# Moteino.net
KiCad netlist of a schematic drawn in EAGLE
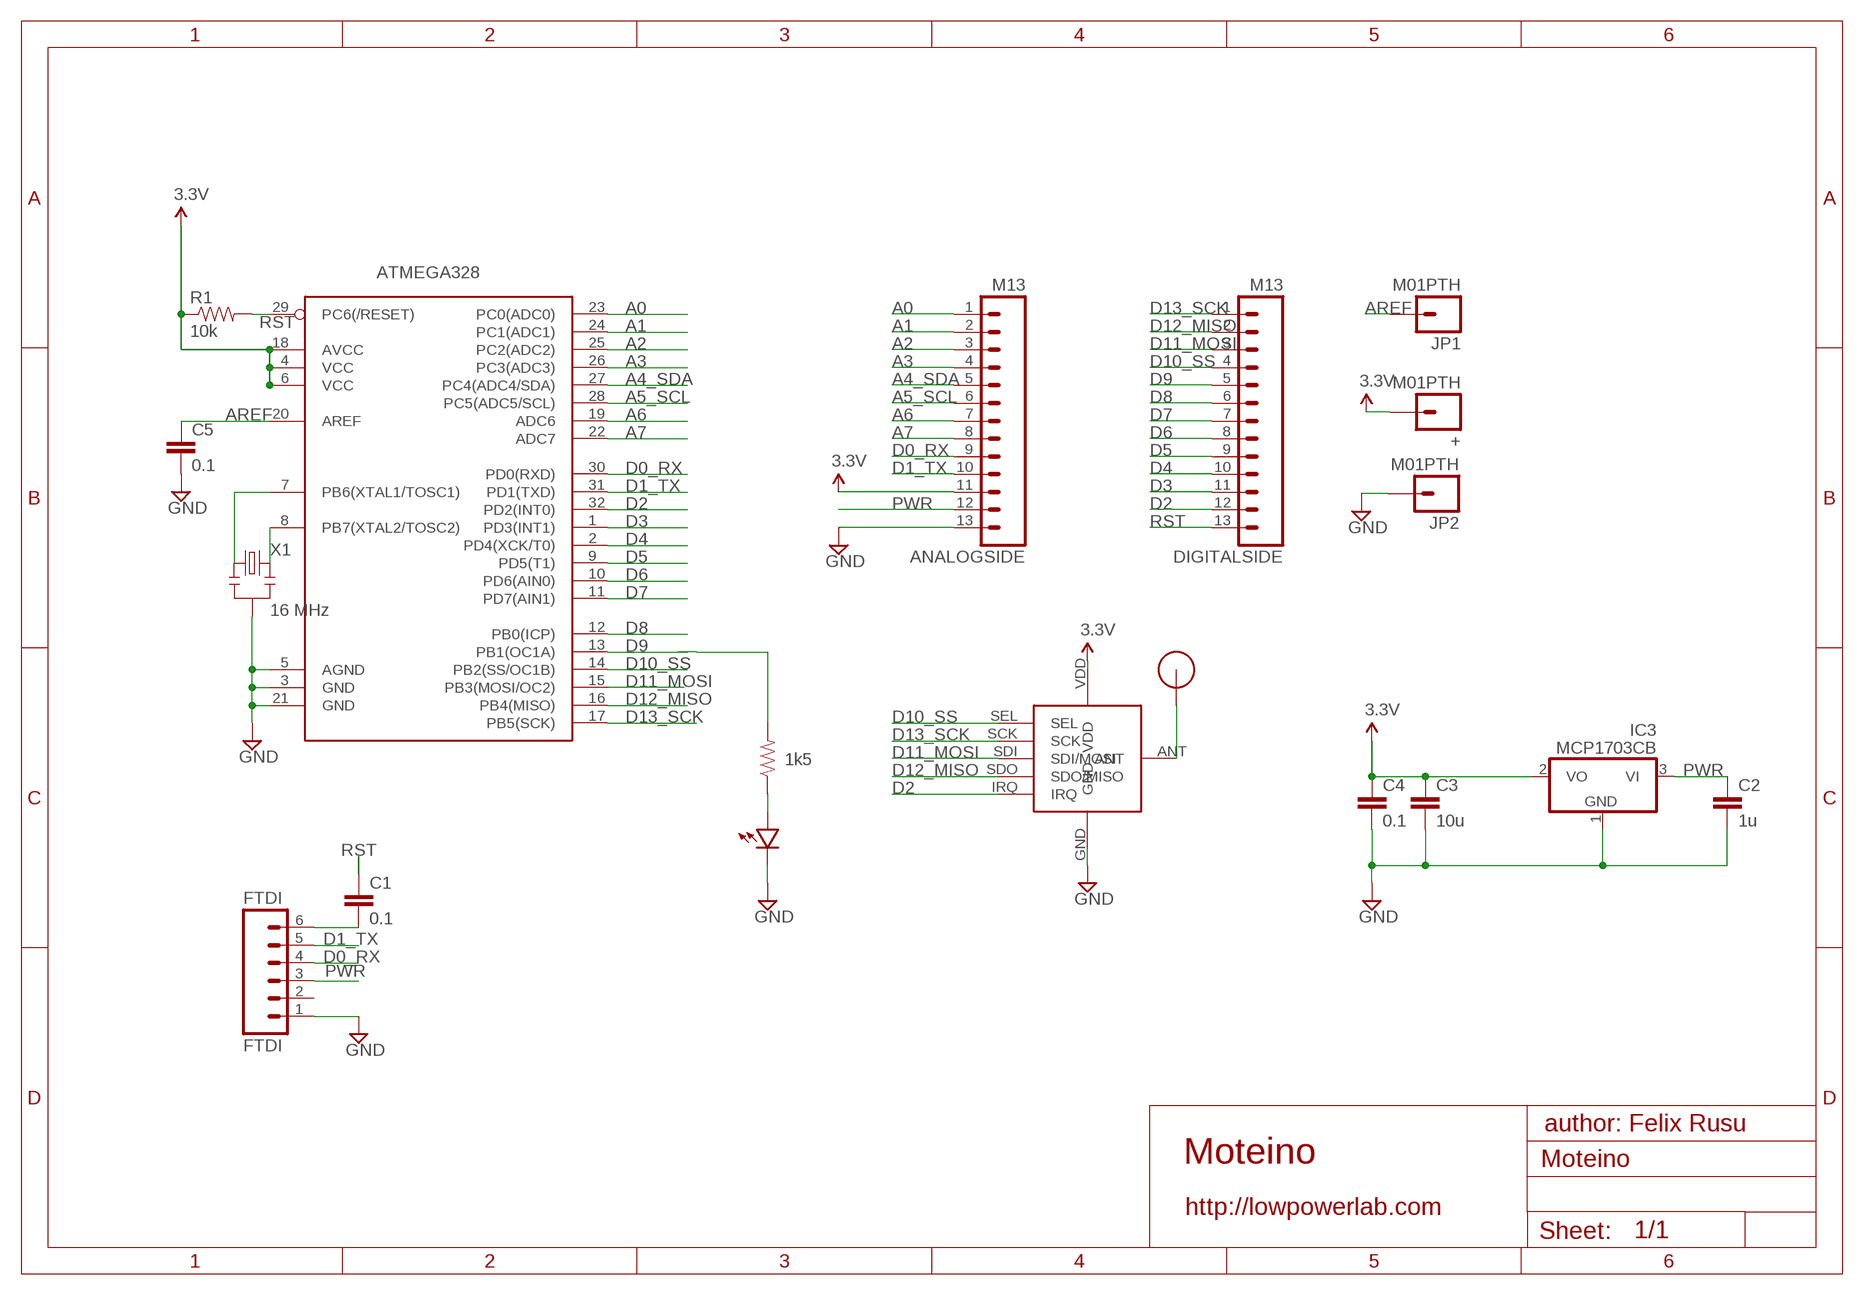
[diagram p0: schematic, sheet 1]

(export (version "E")
  (design (tool "Eeschema 10.0.6"))
  (components
    (comp (ref "+")
      (value "M01PTH")
      (footprint "eagle-import:1X01")
      (libsource (lib "eagle-import") (part "M01PTH"))
    )
    (comp (ref "ANALOGSIDE")
      (value "M13")
      (footprint "eagle-import:1X13")
      (libsource (lib "eagle-import") (part "M13"))
    )
    (comp (ref "ATMEGA328")
      (value "ATMega-328")
      (footprint "eagle-import:TQFP32-08")
      (libsource (lib "eagle-import") (part "ATMEGA168/328TQFP32"))
    )
    (comp (ref "C1")
      (value "0.1")
      (footprint "eagle-import:0603-CAP")
      (libsource (lib "eagle-import") (part "CAP0603-CAP"))
    )
    (comp (ref "C2")
      (value "1u")
      (footprint "eagle-import:0603-CAP")
      (libsource (lib "eagle-import") (part "CAP0603-CAP"))
    )
    (comp (ref "C3")
      (value "10u")
      (footprint "eagle-import:0805-CAP")
      (libsource (lib "eagle-import") (part "CAP0805-CAP"))
    )
    (comp (ref "C4")
      (value "0.1")
      (footprint "eagle-import:0603-CAP")
      (libsource (lib "eagle-import") (part "CAP0603-CAP"))
    )
    (comp (ref "C5")
      (value "0.1")
      (footprint "eagle-import:0603-CAP")
      (libsource (lib "eagle-import") (part "CAP0603-CAP"))
    )
    (comp (ref "DIGITALSIDE")
      (value "M13")
      (footprint "eagle-import:1X13")
      (libsource (lib "eagle-import") (part "M13"))
    )
    (comp (ref "FTDI")
      (value "FTDI")
      (footprint "eagle-import:1X06")
      (libsource (lib "eagle-import") (part "M06SIP"))
    )
    (comp (ref "IC3")
      (value "MCP1703CB")
      (footprint "eagle-import:SOT23")
      (libsource (lib "eagle-import") (part "MCP1703CB"))
    )
    (comp (ref "JP1")
      (value "M01PTH")
      (footprint "eagle-import:1X01")
      (libsource (lib "eagle-import") (part "M01PTH"))
    )
    (comp (ref "JP2")
      (value "M01PTH")
      (footprint "eagle-import:1X01")
      (libsource (lib "eagle-import") (part "M01PTH"))
    )
    (comp (ref "R1")
      (value "10k")
      (footprint "eagle-import:0603-RES")
      (libsource (lib "eagle-import") (part "RESISTOR0603-RES"))
    )
    (comp (ref "R2")
      (value "1k5")
      (footprint "eagle-import:0603-RES")
      (libsource (lib "eagle-import") (part "RESISTOR0603-RES"))
    )
    (comp (ref "RFM12B")
      (value "RFM12B_MINPADS")
      (footprint "eagle-import:RFM12B-MINPADS")
      (libsource (lib "eagle-import") (part "RFM12B_MINPADS"))
    )
    (comp (ref "U$1")
      (value "RFM12B_ANTENNA")
      (footprint "eagle-import:RFM12B-ANTENNA")
      (libsource (lib "eagle-import") (part "RFM12B_ANTENNA"))
    )
    (comp (ref "U$2")
      (value "LED0603")
      (footprint "eagle-import:0603-LED")
      (libsource (lib "eagle-import") (part "LED0603"))
    )
    (comp (ref "X1")
      (value "16 MHz")
      (footprint "eagle-import:RESONATOR-SMD")
      (libsource (lib "eagle-import") (part "RESONATORSMD"))
    )
  )
  (nets
    (net (code "1") (name "/A0") (class "Default")
      (node (ref "ANALOGSIDE") (pin "1") (pinfunction "1_1") (pintype "passive"))
      (node (ref "ATMEGA328") (pin "23") (pinfunction "PC0(ADC0)_23") (pintype "bidirectional"))
    )
    (net (code "2") (name "/A1") (class "Default")
      (node (ref "ANALOGSIDE") (pin "2") (pinfunction "2_2") (pintype "passive"))
      (node (ref "ATMEGA328") (pin "24") (pinfunction "PC1(ADC1)_24") (pintype "bidirectional"))
    )
    (net (code "3") (name "/A2") (class "Default")
      (node (ref "ANALOGSIDE") (pin "3") (pinfunction "3_3") (pintype "passive"))
      (node (ref "ATMEGA328") (pin "25") (pinfunction "PC2(ADC2)_25") (pintype "bidirectional"))
    )
    (net (code "4") (name "/A3") (class "Default")
      (node (ref "ANALOGSIDE") (pin "4") (pinfunction "4_4") (pintype "passive"))
      (node (ref "ATMEGA328") (pin "26") (pinfunction "PC3(ADC3)_26") (pintype "bidirectional"))
    )
    (net (code "5") (name "/A4_SDA") (class "Default")
      (node (ref "ANALOGSIDE") (pin "5") (pinfunction "5_5") (pintype "passive"))
      (node (ref "ATMEGA328") (pin "27") (pinfunction "PC4(ADC4/SDA)_27") (pintype "bidirectional"))
    )
    (net (code "6") (name "/A5_SCL") (class "Default")
      (node (ref "ANALOGSIDE") (pin "6") (pinfunction "6_6") (pintype "passive"))
      (node (ref "ATMEGA328") (pin "28") (pinfunction "PC5(ADC5/SCL)_28") (pintype "bidirectional"))
    )
    (net (code "7") (name "/A6") (class "Default")
      (node (ref "ANALOGSIDE") (pin "7") (pinfunction "7_7") (pintype "passive"))
      (node (ref "ATMEGA328") (pin "19") (pinfunction "ADC6_19") (pintype "bidirectional"))
    )
    (net (code "8") (name "/A7") (class "Default")
      (node (ref "ANALOGSIDE") (pin "8") (pinfunction "8_8") (pintype "passive"))
      (node (ref "ATMEGA328") (pin "22") (pinfunction "ADC7_22") (pintype "bidirectional"))
    )
    (net (code "9") (name "/AREF") (class "Default")
      (node (ref "ATMEGA328") (pin "20") (pinfunction "AREF_20") (pintype "bidirectional"))
      (node (ref "C5") (pin "1") (pinfunction "1_1") (pintype "passive"))
      (node (ref "JP1") (pin "1") (pinfunction "1_1") (pintype "passive"))
    )
    (net (code "10") (name "/D0_RX") (class "Default")
      (node (ref "ANALOGSIDE") (pin "9") (pinfunction "9_9") (pintype "passive"))
      (node (ref "ATMEGA328") (pin "30") (pinfunction "PD0(RXD)_30") (pintype "bidirectional"))
      (node (ref "FTDI") (pin "4") (pinfunction "4_4") (pintype "passive"))
    )
    (net (code "11") (name "/D1_TX") (class "Default")
      (node (ref "ANALOGSIDE") (pin "10") (pinfunction "10_10") (pintype "passive"))
      (node (ref "ATMEGA328") (pin "31") (pinfunction "PD1(TXD)_31") (pintype "bidirectional"))
      (node (ref "FTDI") (pin "5") (pinfunction "5_5") (pintype "passive"))
    )
    (net (code "12") (name "/D2") (class "Default")
      (node (ref "ATMEGA328") (pin "32") (pinfunction "PD2(INT0)_32") (pintype "bidirectional"))
      (node (ref "DIGITALSIDE") (pin "12") (pinfunction "12_12") (pintype "passive"))
      (node (ref "RFM12B") (pin "IRQ") (pinfunction "IRQ_IRQ") (pintype "bidirectional"))
    )
    (net (code "13") (name "/D3") (class "Default")
      (node (ref "ATMEGA328") (pin "1") (pinfunction "PD3(INT1)_1") (pintype "bidirectional"))
      (node (ref "DIGITALSIDE") (pin "11") (pinfunction "11_11") (pintype "passive"))
    )
    (net (code "14") (name "/D4") (class "Default")
      (node (ref "ATMEGA328") (pin "2") (pinfunction "PD4(XCK/T0)_2") (pintype "bidirectional"))
      (node (ref "DIGITALSIDE") (pin "10") (pinfunction "10_10") (pintype "passive"))
    )
    (net (code "15") (name "/D5") (class "Default")
      (node (ref "ATMEGA328") (pin "9") (pinfunction "PD5(T1)_9") (pintype "bidirectional"))
      (node (ref "DIGITALSIDE") (pin "9") (pinfunction "9_9") (pintype "passive"))
    )
    (net (code "16") (name "/D6") (class "Default")
      (node (ref "ATMEGA328") (pin "10") (pinfunction "PD6(AIN0)_10") (pintype "bidirectional"))
      (node (ref "DIGITALSIDE") (pin "8") (pinfunction "8_8") (pintype "passive"))
    )
    (net (code "17") (name "/D7") (class "Default")
      (node (ref "ATMEGA328") (pin "11") (pinfunction "PD7(AIN1)_11") (pintype "bidirectional"))
      (node (ref "DIGITALSIDE") (pin "7") (pinfunction "7_7") (pintype "passive"))
    )
    (net (code "18") (name "/D8") (class "Default")
      (node (ref "ATMEGA328") (pin "12") (pinfunction "PB0(ICP)_12") (pintype "bidirectional"))
      (node (ref "DIGITALSIDE") (pin "6") (pinfunction "6_6") (pintype "passive"))
    )
    (net (code "19") (name "/D9") (class "Default")
      (node (ref "ATMEGA328") (pin "13") (pinfunction "PB1(OC1A)_13") (pintype "bidirectional"))
      (node (ref "DIGITALSIDE") (pin "5") (pinfunction "5_5") (pintype "passive"))
      (node (ref "R2") (pin "2") (pinfunction "2_2") (pintype "passive"))
    )
    (net (code "20") (name "/D10_SS") (class "Default")
      (node (ref "ATMEGA328") (pin "14") (pinfunction "PB2(SS/OC1B)_14") (pintype "bidirectional"))
      (node (ref "DIGITALSIDE") (pin "4") (pinfunction "4_4") (pintype "passive"))
      (node (ref "RFM12B") (pin "SEL") (pinfunction "SEL_SEL") (pintype "bidirectional"))
    )
    (net (code "21") (name "/D11_MOSI") (class "Default")
      (node (ref "ATMEGA328") (pin "15") (pinfunction "PB3(MOSI/OC2)_15") (pintype "bidirectional"))
      (node (ref "DIGITALSIDE") (pin "3") (pinfunction "3_3") (pintype "passive"))
      (node (ref "RFM12B") (pin "SDI") (pinfunction "SDI/MOSI_SDI") (pintype "bidirectional"))
    )
    (net (code "22") (name "/D12_MISO") (class "Default")
      (node (ref "ATMEGA328") (pin "16") (pinfunction "PB4(MISO)_16") (pintype "bidirectional"))
      (node (ref "DIGITALSIDE") (pin "2") (pinfunction "2_2") (pintype "passive"))
      (node (ref "RFM12B") (pin "SDO") (pinfunction "SDO/MISO_SDO") (pintype "bidirectional"))
    )
    (net (code "23") (name "/D13_SCK") (class "Default")
      (node (ref "ATMEGA328") (pin "17") (pinfunction "PB5(SCK)_17") (pintype "bidirectional"))
      (node (ref "DIGITALSIDE") (pin "1") (pinfunction "1_1") (pintype "passive"))
      (node (ref "RFM12B") (pin "SCK") (pinfunction "SCK_SCK") (pintype "bidirectional"))
    )
    (net (code "24") (name "/PWR") (class "Default")
      (node (ref "ANALOGSIDE") (pin "12") (pinfunction "12_12") (pintype "passive"))
      (node (ref "C2") (pin "1") (pinfunction "1_1") (pintype "passive"))
      (node (ref "FTDI") (pin "3") (pinfunction "3_3") (pintype "passive"))
      (node (ref "IC3") (pin "3") (pinfunction "VI_3") (pintype "input"))
    )
    (net (code "25") (name "/RST") (class "Default")
      (node (ref "ATMEGA328") (pin "29") (pinfunction "PC6(/RESET)_29") (pintype "bidirectional"))
      (node (ref "C1") (pin "1") (pinfunction "1_1") (pintype "passive"))
      (node (ref "DIGITALSIDE") (pin "13") (pinfunction "13_13") (pintype "passive"))
      (node (ref "R1") (pin "2") (pinfunction "2_2") (pintype "passive"))
    )
    (net (code "26") (name "3.3V") (class "Default")
      (node (ref "+") (pin "1") (pinfunction "1_1") (pintype "passive"))
      (node (ref "ANALOGSIDE") (pin "11") (pinfunction "11_11") (pintype "passive"))
      (node (ref "ATMEGA328") (pin "18") (pinfunction "AVCC_18") (pintype "bidirectional"))
      (node (ref "ATMEGA328") (pin "4") (pinfunction "VCC_4") (pintype "bidirectional"))
      (node (ref "ATMEGA328") (pin "6") (pinfunction "VCC_6") (pintype "bidirectional"))
      (node (ref "C3") (pin "1") (pinfunction "1_1") (pintype "passive"))
      (node (ref "C4") (pin "1") (pinfunction "1_1") (pintype "passive"))
      (node (ref "IC3") (pin "2") (pinfunction "VO_2") (pintype "passive"))
      (node (ref "R1") (pin "1") (pinfunction "1_1") (pintype "passive"))
      (node (ref "RFM12B") (pin "VDD") (pinfunction "VDD_VDD") (pintype "bidirectional"))
    )
    (net (code "27") (name "GND") (class "Default")
      (node (ref "ANALOGSIDE") (pin "13") (pinfunction "13_13") (pintype "passive"))
      (node (ref "ATMEGA328") (pin "21") (pinfunction "GND_21") (pintype "bidirectional"))
      (node (ref "ATMEGA328") (pin "3") (pinfunction "GND_3") (pintype "bidirectional"))
      (node (ref "ATMEGA328") (pin "5") (pinfunction "AGND_5") (pintype "bidirectional"))
      (node (ref "C2") (pin "2") (pinfunction "2_2") (pintype "passive"))
      (node (ref "C3") (pin "2") (pinfunction "2_2") (pintype "passive"))
      (node (ref "C4") (pin "2") (pinfunction "2_2") (pintype "passive"))
      (node (ref "C5") (pin "2") (pinfunction "2_2") (pintype "passive"))
      (node (ref "FTDI") (pin "1") (pinfunction "1_1") (pintype "passive"))
      (node (ref "IC3") (pin "1") (pinfunction "GND_1") (pintype "passive"))
      (node (ref "JP2") (pin "1") (pinfunction "1_1") (pintype "passive"))
      (node (ref "RFM12B") (pin "GND") (pinfunction "GND_GND") (pintype "bidirectional"))
      (node (ref "U$2") (pin "MINUS") (pinfunction "MINUS_MINUS") (pintype "passive"))
      (node (ref "X1") (pin "2") (pinfunction "2_2") (pintype "passive"))
    )
    (net (code "28") (name "Net-(ATMEGA328-PB6(XTAL1{slash}TOSC1))") (class "Default")
      (node (ref "ATMEGA328") (pin "7") (pinfunction "PB6(XTAL1/TOSC1)_7") (pintype "bidirectional"))
      (node (ref "X1") (pin "1") (pinfunction "1_1") (pintype "passive"))
    )
    (net (code "29") (name "Net-(ATMEGA328-PB7(XTAL2{slash}TOSC2))") (class "Default")
      (node (ref "ATMEGA328") (pin "8") (pinfunction "PB7(XTAL2/TOSC2)_8") (pintype "bidirectional"))
      (node (ref "X1") (pin "3") (pinfunction "3_3") (pintype "passive"))
    )
    (net (code "30") (name "Net-(C1-Pad2)") (class "Default")
      (node (ref "C1") (pin "2") (pinfunction "2_2") (pintype "passive"))
      (node (ref "FTDI") (pin "6") (pinfunction "6_6") (pintype "passive"))
    )
    (net (code "31") (name "Net-(R2-Pad1)") (class "Default")
      (node (ref "R2") (pin "1") (pinfunction "1_1") (pintype "passive"))
      (node (ref "U$2") (pin "PLUS") (pinfunction "PLUS_PLUS") (pintype "passive"))
    )
    (net (code "32") (name "Net-(U$1-1)") (class "Default")
      (node (ref "RFM12B") (pin "ANT") (pinfunction "ANT_ANT") (pintype "bidirectional"))
      (node (ref "U$1") (pin "P$1") (pinfunction "1_P$1") (pintype "bidirectional"))
    )
    (net (code "33") (name "unconnected-(FTDI-Pad2)") (class "Default")
      (node (ref "FTDI") (pin "2") (pinfunction "2_2") (pintype "passive"))
    )
  )
)
